# sender.net
KiCad netlist of a schematic drawn in EAGLE
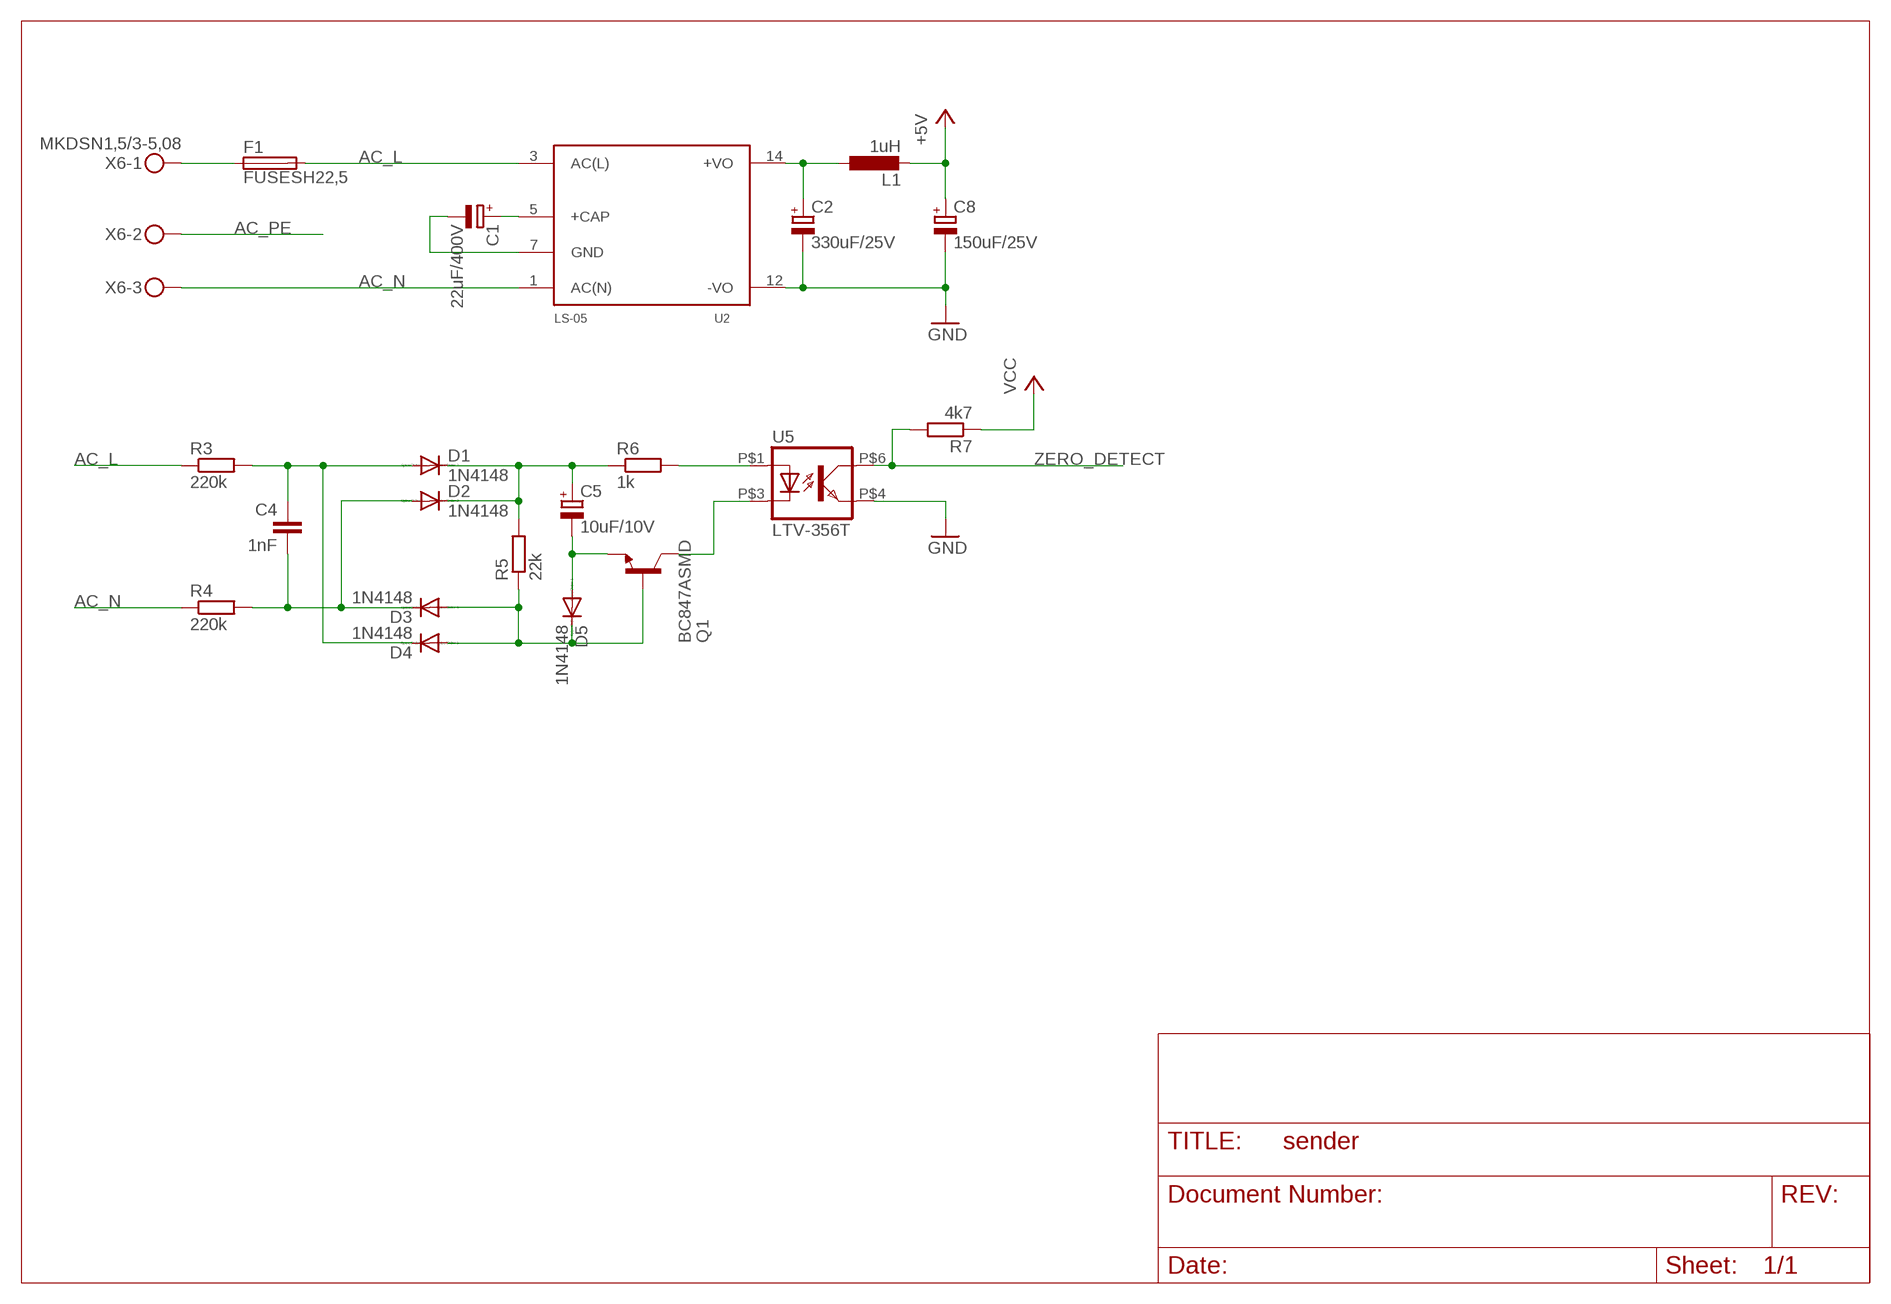
[diagram p0: schematic, sheet 1]

(export (version "E")
  (design (tool "Eeschema 10.0.6"))
  (components
    (comp (ref "C1")
      (value "22uF/400V")
      (footprint "eagle-import:E7,5-16")
      (libsource (lib "eagle-import") (part "CPOL-EUE7.5-16"))
    )
    (comp (ref "C2")
      (value "330uF/25V")
      (footprint "eagle-import:150CLZ-1010")
      (libsource (lib "eagle-import") (part "CPOL-EU150CLZ-1010"))
    )
    (comp (ref "C4")
      (value "1nF")
      (footprint "eagle-import:C050-050X075")
      (libsource (lib "eagle-import") (part "C-EU050-050X075"))
    )
    (comp (ref "C5")
      (value "10uF/10V")
      (footprint "eagle-import:153CLV-0505")
      (libsource (lib "eagle-import") (part "CPOL-EU153CLV-0505"))
    )
    (comp (ref "C8")
      (value "150uF/25V")
      (footprint "eagle-import:153CLV-0810")
      (libsource (lib "eagle-import") (part "CPOL-EU153CLV-0810"))
    )
    (comp (ref "D1")
      (value "1N4148")
      (footprint "eagle-import:SOD323-W")
      (libsource (lib "eagle-import") (part "DIODE-SOD323-W"))
    )
    (comp (ref "D2")
      (value "1N4148")
      (footprint "eagle-import:SOD323-W")
      (libsource (lib "eagle-import") (part "DIODE-SOD323-W"))
    )
    (comp (ref "D3")
      (value "1N4148")
      (footprint "eagle-import:SOD323-W")
      (libsource (lib "eagle-import") (part "DIODE-SOD323-W"))
    )
    (comp (ref "D4")
      (value "1N4148")
      (footprint "eagle-import:SOD323-W")
      (libsource (lib "eagle-import") (part "DIODE-SOD323-W"))
    )
    (comp (ref "D5")
      (value "1N4148")
      (footprint "eagle-import:SOD323-W")
      (libsource (lib "eagle-import") (part "DIODE-SOD323-W"))
    )
    (comp (ref "F1")
      (value "FUSESH22,5")
      (footprint "eagle-import:SH22,5")
      (libsource (lib "eagle-import") (part "FUSESH22,5"))
    )
    (comp (ref "L1")
      (value "1uH")
      (footprint "eagle-import:L3225P")
      (libsource (lib "eagle-import") (part "L-EUL3225P"))
    )
    (comp (ref "Q1")
      (value "BC847ASMD")
      (footprint "eagle-import:SOT23")
      (libsource (lib "eagle-import") (part "BC847SMDA"))
    )
    (comp (ref "R3")
      (value "220k")
      (footprint "eagle-import:R0603")
      (libsource (lib "eagle-import") (part "R-EU_R0603"))
    )
    (comp (ref "R4")
      (value "220k")
      (footprint "eagle-import:R0603")
      (libsource (lib "eagle-import") (part "R-EU_R0603"))
    )
    (comp (ref "R5")
      (value "22k")
      (footprint "eagle-import:R0603")
      (libsource (lib "eagle-import") (part "R-EU_R0603"))
    )
    (comp (ref "R6")
      (value "1k")
      (footprint "eagle-import:R0603")
      (libsource (lib "eagle-import") (part "R-EU_R0603"))
    )
    (comp (ref "R7")
      (value "4k7")
      (footprint "eagle-import:R0603")
      (libsource (lib "eagle-import") (part "R-EU_R0603"))
    )
    (comp (ref "U2")
      (value "LS-05")
      (footprint "eagle-import:LS-05")
      (libsource (lib "eagle-import") (part "LS-05"))
    )
    (comp (ref "U5")
      (value "LTV-356T")
      (footprint "eagle-import:SMD")
      (libsource (lib "eagle-import") (part "LTV-356T"))
    )
    (comp (ref "X6")
      (value "MKDSN1,5/3-5,08")
      (footprint "eagle-import:MKDSN1,5_3-5,08")
      (libsource (lib "eagle-import") (part "MKDSN1,5/3-5,08"))
    )
  )
  (nets
    (net (code "1") (name "+5V") (class "Default")
      (node (ref "C8") (pin "+") (pinfunction "+_+") (pintype "passive"))
      (node (ref "L1") (pin "2") (pinfunction "2_2") (pintype "passive"))
    )
    (net (code "2") (name "/AC_L") (class "Default")
      (node (ref "F1") (pin "2") (pinfunction "2_2") (pintype "passive"))
      (node (ref "R3") (pin "1") (pinfunction "1_1") (pintype "passive"))
      (node (ref "U2") (pin "3") (pinfunction "AC(L)_3") (pintype "bidirectional"))
    )
    (net (code "3") (name "/AC_N") (class "Default")
      (node (ref "R4") (pin "1") (pinfunction "1_1") (pintype "passive"))
      (node (ref "U2") (pin "1") (pinfunction "AC(N)_1") (pintype "bidirectional"))
      (node (ref "X6") (pin "3") (pinfunction "KL_3") (pintype "passive"))
    )
    (net (code "4") (name "/AC_PE") (class "Default")
      (node (ref "X6") (pin "2") (pinfunction "KL_2") (pintype "passive"))
    )
    (net (code "5") (name "/ZERO_DETECT") (class "Default")
      (node (ref "R7") (pin "2") (pinfunction "2_2") (pintype "passive"))
      (node (ref "U5") (pin "P$6") (pinfunction "COL_P$6") (pintype "passive"))
    )
    (net (code "6") (name "GND") (class "Default")
      (node (ref "C2") (pin "-") (pinfunction "-_-") (pintype "passive"))
      (node (ref "C8") (pin "-") (pinfunction "-_-") (pintype "passive"))
      (node (ref "U2") (pin "12") (pinfunction "-VO_12") (pintype "bidirectional"))
      (node (ref "U5") (pin "P$4") (pinfunction "EMIT_P$4") (pintype "passive"))
    )
    (net (code "7") (name "Net-(C4-Pad1)") (class "Default")
      (node (ref "C4") (pin "1") (pinfunction "1_1") (pintype "passive"))
      (node (ref "D1") (pin "A") (pinfunction "A_A") (pintype "passive"))
      (node (ref "D4") (pin "C") (pinfunction "C_C") (pintype "passive"))
      (node (ref "R3") (pin "2") (pinfunction "2_2") (pintype "passive"))
    )
    (net (code "8") (name "Net-(C4-Pad2)") (class "Default")
      (node (ref "C4") (pin "2") (pinfunction "2_2") (pintype "passive"))
      (node (ref "D2") (pin "A") (pinfunction "A_A") (pintype "passive"))
      (node (ref "D3") (pin "C") (pinfunction "C_C") (pintype "passive"))
      (node (ref "R4") (pin "2") (pinfunction "2_2") (pintype "passive"))
    )
    (net (code "9") (name "Net-(C5-Pad+)") (class "Default")
      (node (ref "C5") (pin "+") (pinfunction "+_+") (pintype "passive"))
      (node (ref "D1") (pin "C") (pinfunction "C_C") (pintype "passive"))
      (node (ref "D2") (pin "C") (pinfunction "C_C") (pintype "passive"))
      (node (ref "R5") (pin "2") (pinfunction "2_2") (pintype "passive"))
      (node (ref "R6") (pin "1") (pinfunction "1_1") (pintype "passive"))
    )
    (net (code "10") (name "Net-(Q1-B)") (class "Default")
      (node (ref "D3") (pin "A") (pinfunction "A_A") (pintype "passive"))
      (node (ref "D4") (pin "A") (pinfunction "A_A") (pintype "passive"))
      (node (ref "D5") (pin "C") (pinfunction "C_C") (pintype "passive"))
      (node (ref "Q1") (pin "1") (pinfunction "B_1") (pintype "passive"))
      (node (ref "R5") (pin "1") (pinfunction "1_1") (pintype "passive"))
    )
    (net (code "11") (name "Net-(Q1-C)") (class "Default")
      (node (ref "Q1") (pin "3") (pinfunction "C_3") (pintype "passive"))
      (node (ref "U5") (pin "P$3") (pinfunction "C_P$3") (pintype "passive"))
    )
    (net (code "12") (name "Net-(Q1-E)") (class "Default")
      (node (ref "C5") (pin "-") (pinfunction "-_-") (pintype "passive"))
      (node (ref "D5") (pin "A") (pinfunction "A_A") (pintype "passive"))
      (node (ref "Q1") (pin "2") (pinfunction "E_2") (pintype "passive"))
    )
    (net (code "13") (name "Net-(U2-+CAP)") (class "Default")
      (node (ref "C1") (pin "+") (pinfunction "+_+") (pintype "passive"))
      (node (ref "U2") (pin "5") (pinfunction "+CAP_5") (pintype "bidirectional"))
    )
    (net (code "14") (name "Net-(U2-+VO)") (class "Default")
      (node (ref "C2") (pin "+") (pinfunction "+_+") (pintype "passive"))
      (node (ref "L1") (pin "1") (pinfunction "1_1") (pintype "passive"))
      (node (ref "U2") (pin "14") (pinfunction "+VO_14") (pintype "bidirectional"))
    )
    (net (code "15") (name "Net-(U2-GND)") (class "Default")
      (node (ref "C1") (pin "-") (pinfunction "-_-") (pintype "passive"))
      (node (ref "U2") (pin "7") (pinfunction "GND_7") (pintype "bidirectional"))
    )
    (net (code "16") (name "Net-(U5-A)") (class "Default")
      (node (ref "R6") (pin "2") (pinfunction "2_2") (pintype "passive"))
      (node (ref "U5") (pin "P$1") (pinfunction "A_P$1") (pintype "passive"))
    )
    (net (code "17") (name "Net-(X6A-KL)") (class "Default")
      (node (ref "F1") (pin "1") (pinfunction "1_1") (pintype "passive"))
      (node (ref "X6") (pin "1") (pinfunction "KL_1") (pintype "passive"))
    )
    (net (code "18") (name "VCC") (class "Default")
      (node (ref "R7") (pin "1") (pinfunction "1_1") (pintype "passive"))
    )
  )
)
